# 2_Connectors.net
KiCad netlist of a schematic drawn in Altium Designer
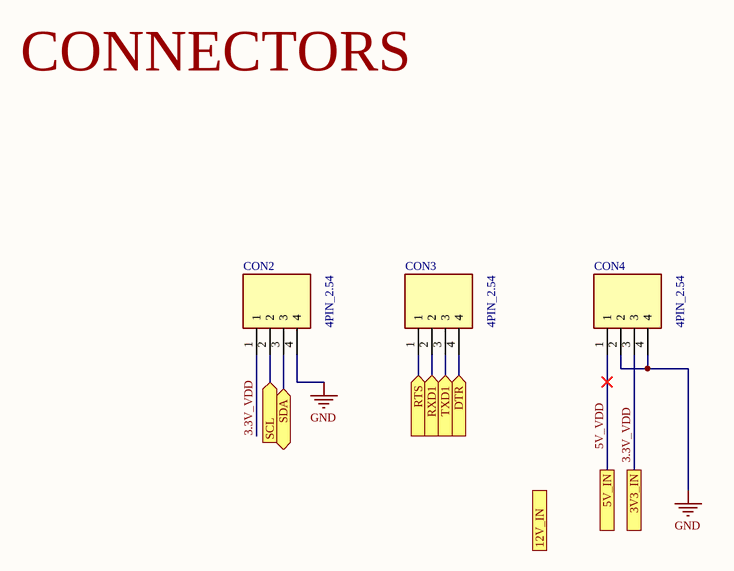
[diagram p0: 2.Connectors.SchDoc]

(export (version "E")
  (design (tool "Eeschema 10.0.6"))
  (components
    (comp (ref "CON2")
      (value "4PIN_2.54")
      (footprint "PcbLib:4Pin_2.5")
      (libsource (lib "Schlib") (part "4PIN_2.54"))
    )
    (comp (ref "CON3")
      (value "4PIN_2.54")
      (footprint "PcbLib:4Pin_2.5")
      (libsource (lib "Schlib") (part "4PIN_2.54"))
    )
    (comp (ref "CON4")
      (value "4PIN_2.54")
      (footprint "PcbLib:4Pin_2.5")
      (libsource (lib "Schlib") (part "4PIN_2.54"))
    )
  )
  (nets
    (net (code "1") (name "/3.3V_VDD") (class "Default")
      (node (ref "CON2") (pin "1") (pinfunction "1_1") (pintype "passive"))
      (node (ref "CON4") (pin "3") (pinfunction "3_3") (pintype "passive"))
    )
    (net (code "2") (name "/5V_VDD") (class "Default")
      (node (ref "CON4") (pin "1") (pinfunction "1_1") (pintype "passive"))
    )
    (net (code "4") (name "/DTR") (class "Default")
      (node (ref "CON3") (pin "4") (pinfunction "4_4") (pintype "passive"))
    )
    (net (code "5") (name "/RTS") (class "Default")
      (node (ref "CON3") (pin "1") (pinfunction "1_1") (pintype "passive"))
    )
    (net (code "6") (name "/RXD1") (class "Default")
      (node (ref "CON3") (pin "2") (pinfunction "2_2") (pintype "passive"))
    )
    (net (code "7") (name "/SCL") (class "Default")
      (node (ref "CON2") (pin "2") (pinfunction "2_2") (pintype "passive"))
    )
    (net (code "8") (name "/SDA") (class "Default")
      (node (ref "CON2") (pin "3") (pinfunction "3_3") (pintype "passive"))
    )
    (net (code "9") (name "/TXD1") (class "Default")
      (node (ref "CON3") (pin "3") (pinfunction "3_3") (pintype "passive"))
    )
    (net (code "10") (name "GND") (class "Default")
      (node (ref "CON2") (pin "4") (pinfunction "4_4") (pintype "passive"))
      (node (ref "CON4") (pin "2") (pinfunction "2_2") (pintype "passive"))
      (node (ref "CON4") (pin "4") (pinfunction "4_4") (pintype "passive"))
    )
  )
)
